# RS485_Clock.net
KiCad netlist of a schematic drawn in Altium Designer
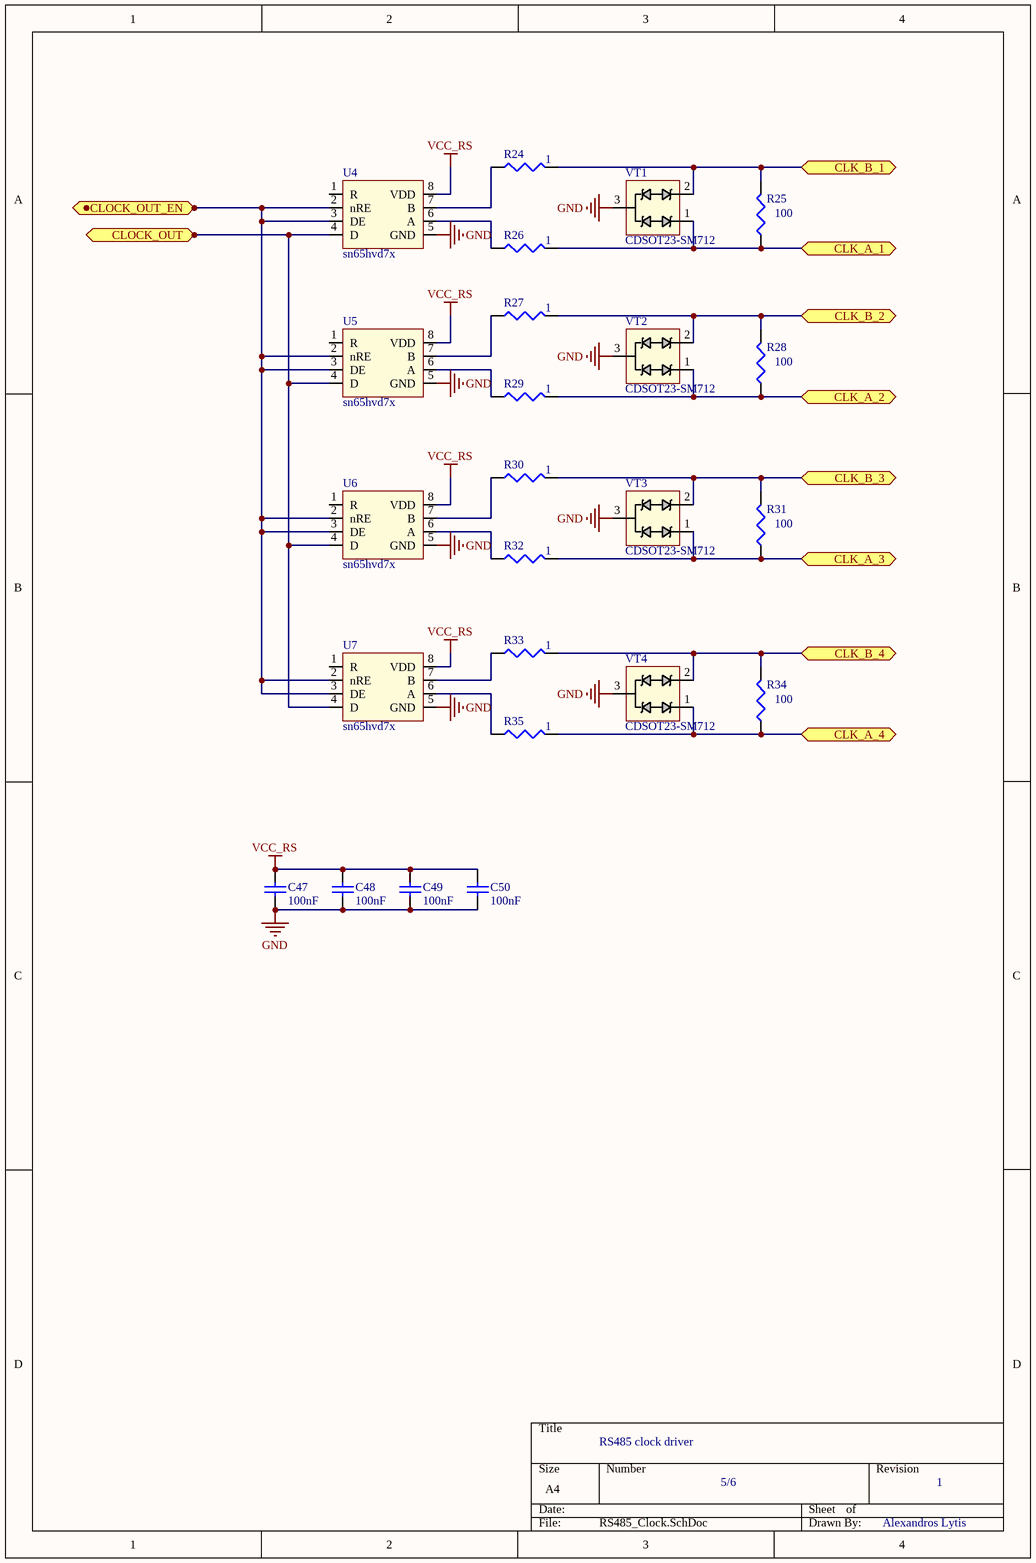
[diagram p0: RS485_Clock.SchDoc]

(export (version "E")
  (design (tool "Eeschema 10.0.6"))
  (components
    (comp (ref "C47")
      (value "100nF")
      (footprint "CAP0603")
      (description "Capacitor (Semiconductor SIM Model)")
      (fields (field (name "Comment") "Cap Semi") (field (name "PUBLISHER") "Altium Limited"))
      (libsource (lib "Miscellaneous Devices") (part "Cap Semi"))
    )
    (comp (ref "C48")
      (value "100nF")
      (footprint "CAP0603")
      (description "Capacitor (Semiconductor SIM Model)")
      (fields (field (name "Comment") "Cap Semi") (field (name "PUBLISHER") "Altium Limited"))
      (libsource (lib "Miscellaneous Devices") (part "Cap Semi"))
    )
    (comp (ref "C49")
      (value "100nF")
      (footprint "CAP0603")
      (description "Capacitor (Semiconductor SIM Model)")
      (fields (field (name "Comment") "Cap Semi") (field (name "PUBLISHER") "Altium Limited"))
      (libsource (lib "Miscellaneous Devices") (part "Cap Semi"))
    )
    (comp (ref "C50")
      (value "100nF")
      (footprint "CAP0603")
      (description "Capacitor (Semiconductor SIM Model)")
      (fields (field (name "Comment") "Cap Semi") (field (name "PUBLISHER") "Altium Limited"))
      (libsource (lib "Miscellaneous Devices") (part "Cap Semi"))
    )
    (comp (ref "R24")
      (value "1")
      (footprint "RES0603")
      (description "Resistor")
      (fields (field (name "Comment") "p-p") (field (name "PUBLISHER") "Altium Limited"))
      (libsource (lib "Miscellaneous Devices") (part "Res3"))
    )
    (comp (ref "R25")
      (value "100")
      (footprint "RES0603")
      (description "Resistor")
      (fields (field (name "Comment") "p-p") (field (name "PUBLISHER") "Altium Limited"))
      (libsource (lib "Miscellaneous Devices") (part "Res3"))
    )
    (comp (ref "R26")
      (value "1")
      (footprint "RES0603")
      (description "Resistor")
      (fields (field (name "Comment") "p-p") (field (name "PUBLISHER") "Altium Limited"))
      (libsource (lib "Miscellaneous Devices") (part "Res3"))
    )
    (comp (ref "R27")
      (value "1")
      (footprint "RES0603")
      (description "Resistor")
      (fields (field (name "Comment") "p-p") (field (name "PUBLISHER") "Altium Limited"))
      (libsource (lib "Miscellaneous Devices") (part "Res3"))
    )
    (comp (ref "R28")
      (value "100")
      (footprint "RES0603")
      (description "Resistor")
      (fields (field (name "Comment") "p-p") (field (name "PUBLISHER") "Altium Limited"))
      (libsource (lib "Miscellaneous Devices") (part "Res3"))
    )
    (comp (ref "R29")
      (value "1")
      (footprint "RES0603")
      (description "Resistor")
      (fields (field (name "Comment") "p-p") (field (name "PUBLISHER") "Altium Limited"))
      (libsource (lib "Miscellaneous Devices") (part "Res3"))
    )
    (comp (ref "R30")
      (value "1")
      (footprint "RES0603")
      (description "Resistor")
      (fields (field (name "Comment") "p-p") (field (name "PUBLISHER") "Altium Limited"))
      (libsource (lib "Miscellaneous Devices") (part "Res3"))
    )
    (comp (ref "R31")
      (value "100")
      (footprint "RES0603")
      (description "Resistor")
      (fields (field (name "Comment") "p-p") (field (name "PUBLISHER") "Altium Limited"))
      (libsource (lib "Miscellaneous Devices") (part "Res3"))
    )
    (comp (ref "R32")
      (value "1")
      (footprint "RES0603")
      (description "Resistor")
      (fields (field (name "Comment") "p-p") (field (name "PUBLISHER") "Altium Limited"))
      (libsource (lib "Miscellaneous Devices") (part "Res3"))
    )
    (comp (ref "R33")
      (value "1")
      (footprint "RES0603")
      (description "Resistor")
      (fields (field (name "Comment") "p-p") (field (name "PUBLISHER") "Altium Limited"))
      (libsource (lib "Miscellaneous Devices") (part "Res3"))
    )
    (comp (ref "R34")
      (value "100")
      (footprint "RES0603")
      (description "Resistor")
      (fields (field (name "Comment") "p-p") (field (name "PUBLISHER") "Altium Limited"))
      (libsource (lib "Miscellaneous Devices") (part "Res3"))
    )
    (comp (ref "R35")
      (value "1")
      (footprint "RES0603")
      (description "Resistor")
      (fields (field (name "Comment") "p-p") (field (name "PUBLISHER") "Altium Limited"))
      (libsource (lib "Miscellaneous Devices") (part "Res3"))
    )
    (comp (ref "U4")
      (value "sn65hvd7x")
      (footprint "SOP127P600-8N")
      (libsource (lib "Custom_Libraries") (part "sn65hvd7x"))
    )
    (comp (ref "U5")
      (value "sn65hvd7x")
      (footprint "SOP127P600-8N")
      (libsource (lib "Custom_Libraries") (part "sn65hvd7x"))
    )
    (comp (ref "U6")
      (value "sn65hvd7x")
      (footprint "SOP127P600-8N")
      (libsource (lib "Custom_Libraries") (part "sn65hvd7x"))
    )
    (comp (ref "U7")
      (value "sn65hvd7x")
      (footprint "SOP127P600-8N")
      (libsource (lib "Custom_Libraries") (part "sn65hvd7x"))
    )
    (comp (ref "VT1")
      (value "CDSOT23-SM712")
      (footprint "SOT190P230X117-3N")
      (libsource (lib "Custom_Libraries") (part "CDSOT23-SM712"))
    )
    (comp (ref "VT2")
      (value "CDSOT23-SM712")
      (footprint "SOT190P230X117-3N")
      (libsource (lib "Custom_Libraries") (part "CDSOT23-SM712"))
    )
    (comp (ref "VT3")
      (value "CDSOT23-SM712")
      (footprint "SOT190P230X117-3N")
      (libsource (lib "Custom_Libraries") (part "CDSOT23-SM712"))
    )
    (comp (ref "VT4")
      (value "CDSOT23-SM712")
      (footprint "SOT190P230X117-3N")
      (libsource (lib "Custom_Libraries") (part "CDSOT23-SM712"))
    )
  )
  (nets
    (net (code "1") (name "/CLK_A_1") (class "Default")
      (node (ref "R25") (pin "1") (pinfunction "1_1") (pintype "passive"))
      (node (ref "R26") (pin "2") (pinfunction "2_2") (pintype "passive"))
      (node (ref "VT1") (pin "1") (pintype "passive"))
    )
    (net (code "2") (name "/CLK_A_2") (class "Default")
      (node (ref "R28") (pin "1") (pinfunction "1_1") (pintype "passive"))
      (node (ref "R29") (pin "2") (pinfunction "2_2") (pintype "passive"))
      (node (ref "VT2") (pin "1") (pintype "passive"))
    )
    (net (code "3") (name "/CLK_A_3") (class "Default")
      (node (ref "R31") (pin "1") (pinfunction "1_1") (pintype "passive"))
      (node (ref "R32") (pin "2") (pinfunction "2_2") (pintype "passive"))
      (node (ref "VT3") (pin "1") (pintype "passive"))
    )
    (net (code "4") (name "/CLK_A_4") (class "Default")
      (node (ref "R34") (pin "1") (pinfunction "1_1") (pintype "passive"))
      (node (ref "R35") (pin "2") (pinfunction "2_2") (pintype "passive"))
      (node (ref "VT4") (pin "1") (pintype "passive"))
    )
    (net (code "5") (name "/CLK_B_1") (class "Default")
      (node (ref "R24") (pin "2") (pinfunction "2_2") (pintype "passive"))
      (node (ref "R25") (pin "2") (pinfunction "2_2") (pintype "passive"))
      (node (ref "VT1") (pin "2") (pintype "passive"))
    )
    (net (code "6") (name "/CLK_B_2") (class "Default")
      (node (ref "R27") (pin "2") (pinfunction "2_2") (pintype "passive"))
      (node (ref "R28") (pin "2") (pinfunction "2_2") (pintype "passive"))
      (node (ref "VT2") (pin "2") (pintype "passive"))
    )
    (net (code "7") (name "/CLK_B_3") (class "Default")
      (node (ref "R30") (pin "2") (pinfunction "2_2") (pintype "passive"))
      (node (ref "R31") (pin "2") (pinfunction "2_2") (pintype "passive"))
      (node (ref "VT3") (pin "2") (pintype "passive"))
    )
    (net (code "8") (name "/CLK_B_4") (class "Default")
      (node (ref "R33") (pin "2") (pinfunction "2_2") (pintype "passive"))
      (node (ref "R34") (pin "2") (pinfunction "2_2") (pintype "passive"))
      (node (ref "VT4") (pin "2") (pintype "passive"))
    )
    (net (code "9") (name "/CLOCK_OUT") (class "Default")
      (node (ref "U4") (pin "4") (pinfunction "D_4") (pintype "passive"))
      (node (ref "U5") (pin "4") (pinfunction "D_4") (pintype "passive"))
      (node (ref "U6") (pin "4") (pinfunction "D_4") (pintype "passive"))
      (node (ref "U7") (pin "4") (pinfunction "D_4") (pintype "passive"))
    )
    (net (code "10") (name "/CLOCK_OUT_EN") (class "Default")
      (node (ref "U4") (pin "2") (pinfunction "nRE_2") (pintype "passive"))
      (node (ref "U4") (pin "3") (pinfunction "DE_3") (pintype "passive"))
      (node (ref "U5") (pin "2") (pinfunction "nRE_2") (pintype "passive"))
      (node (ref "U5") (pin "3") (pinfunction "DE_3") (pintype "passive"))
      (node (ref "U6") (pin "2") (pinfunction "nRE_2") (pintype "passive"))
      (node (ref "U6") (pin "3") (pinfunction "DE_3") (pintype "passive"))
      (node (ref "U7") (pin "2") (pinfunction "nRE_2") (pintype "passive"))
      (node (ref "U7") (pin "3") (pinfunction "DE_3") (pintype "passive"))
    )
    (net (code "11") (name "GND") (class "Default")
      (node (ref "C47") (pin "1") (pinfunction "1_1") (pintype "passive"))
      (node (ref "C48") (pin "1") (pinfunction "1_1") (pintype "passive"))
      (node (ref "C49") (pin "1") (pinfunction "1_1") (pintype "passive"))
      (node (ref "C50") (pin "1") (pinfunction "1_1") (pintype "passive"))
      (node (ref "U4") (pin "5") (pinfunction "GND_5") (pintype "passive"))
      (node (ref "U5") (pin "5") (pinfunction "GND_5") (pintype "passive"))
      (node (ref "U6") (pin "5") (pinfunction "GND_5") (pintype "passive"))
      (node (ref "U7") (pin "5") (pinfunction "GND_5") (pintype "passive"))
      (node (ref "VT1") (pin "3") (pintype "passive"))
      (node (ref "VT2") (pin "3") (pintype "passive"))
      (node (ref "VT3") (pin "3") (pintype "passive"))
      (node (ref "VT4") (pin "3") (pintype "passive"))
    )
    (net (code "12") (name "Net-(U4-A)") (class "Default")
      (node (ref "R26") (pin "1") (pinfunction "1_1") (pintype "passive"))
      (node (ref "U4") (pin "6") (pinfunction "A_6") (pintype "passive"))
    )
    (net (code "13") (name "Net-(U4-B)") (class "Default")
      (node (ref "R24") (pin "1") (pinfunction "1_1") (pintype "passive"))
      (node (ref "U4") (pin "7") (pinfunction "B_7") (pintype "passive"))
    )
    (net (code "14") (name "Net-(U5-A)") (class "Default")
      (node (ref "R29") (pin "1") (pinfunction "1_1") (pintype "passive"))
      (node (ref "U5") (pin "6") (pinfunction "A_6") (pintype "passive"))
    )
    (net (code "15") (name "Net-(U5-B)") (class "Default")
      (node (ref "R27") (pin "1") (pinfunction "1_1") (pintype "passive"))
      (node (ref "U5") (pin "7") (pinfunction "B_7") (pintype "passive"))
    )
    (net (code "16") (name "Net-(U6-A)") (class "Default")
      (node (ref "R32") (pin "1") (pinfunction "1_1") (pintype "passive"))
      (node (ref "U6") (pin "6") (pinfunction "A_6") (pintype "passive"))
    )
    (net (code "17") (name "Net-(U6-B)") (class "Default")
      (node (ref "R30") (pin "1") (pinfunction "1_1") (pintype "passive"))
      (node (ref "U6") (pin "7") (pinfunction "B_7") (pintype "passive"))
    )
    (net (code "18") (name "Net-(U7-A)") (class "Default")
      (node (ref "R35") (pin "1") (pinfunction "1_1") (pintype "passive"))
      (node (ref "U7") (pin "6") (pinfunction "A_6") (pintype "passive"))
    )
    (net (code "19") (name "Net-(U7-B)") (class "Default")
      (node (ref "R33") (pin "1") (pinfunction "1_1") (pintype "passive"))
      (node (ref "U7") (pin "7") (pinfunction "B_7") (pintype "passive"))
    )
    (net (code "20") (name "VCC_RS") (class "Default")
      (node (ref "C47") (pin "2") (pinfunction "2_2") (pintype "passive"))
      (node (ref "C48") (pin "2") (pinfunction "2_2") (pintype "passive"))
      (node (ref "C49") (pin "2") (pinfunction "2_2") (pintype "passive"))
      (node (ref "C50") (pin "2") (pinfunction "2_2") (pintype "passive"))
      (node (ref "U4") (pin "8") (pinfunction "VDD_8") (pintype "passive"))
      (node (ref "U5") (pin "8") (pinfunction "VDD_8") (pintype "passive"))
      (node (ref "U6") (pin "8") (pinfunction "VDD_8") (pintype "passive"))
      (node (ref "U7") (pin "8") (pinfunction "VDD_8") (pintype "passive"))
    )
    (net (code "21") (name "unconnected-(U4-R-Pad1)") (class "Default")
      (node (ref "U4") (pin "1") (pinfunction "R_1") (pintype "passive"))
    )
    (net (code "22") (name "unconnected-(U5-R-Pad1)") (class "Default")
      (node (ref "U5") (pin "1") (pinfunction "R_1") (pintype "passive"))
    )
    (net (code "23") (name "unconnected-(U6-R-Pad1)") (class "Default")
      (node (ref "U6") (pin "1") (pinfunction "R_1") (pintype "passive"))
    )
    (net (code "24") (name "unconnected-(U7-R-Pad1)") (class "Default")
      (node (ref "U7") (pin "1") (pinfunction "R_1") (pintype "passive"))
    )
  )
)
